# scartboard-rework.net
KiCad netlist of a schematic drawn in EAGLE
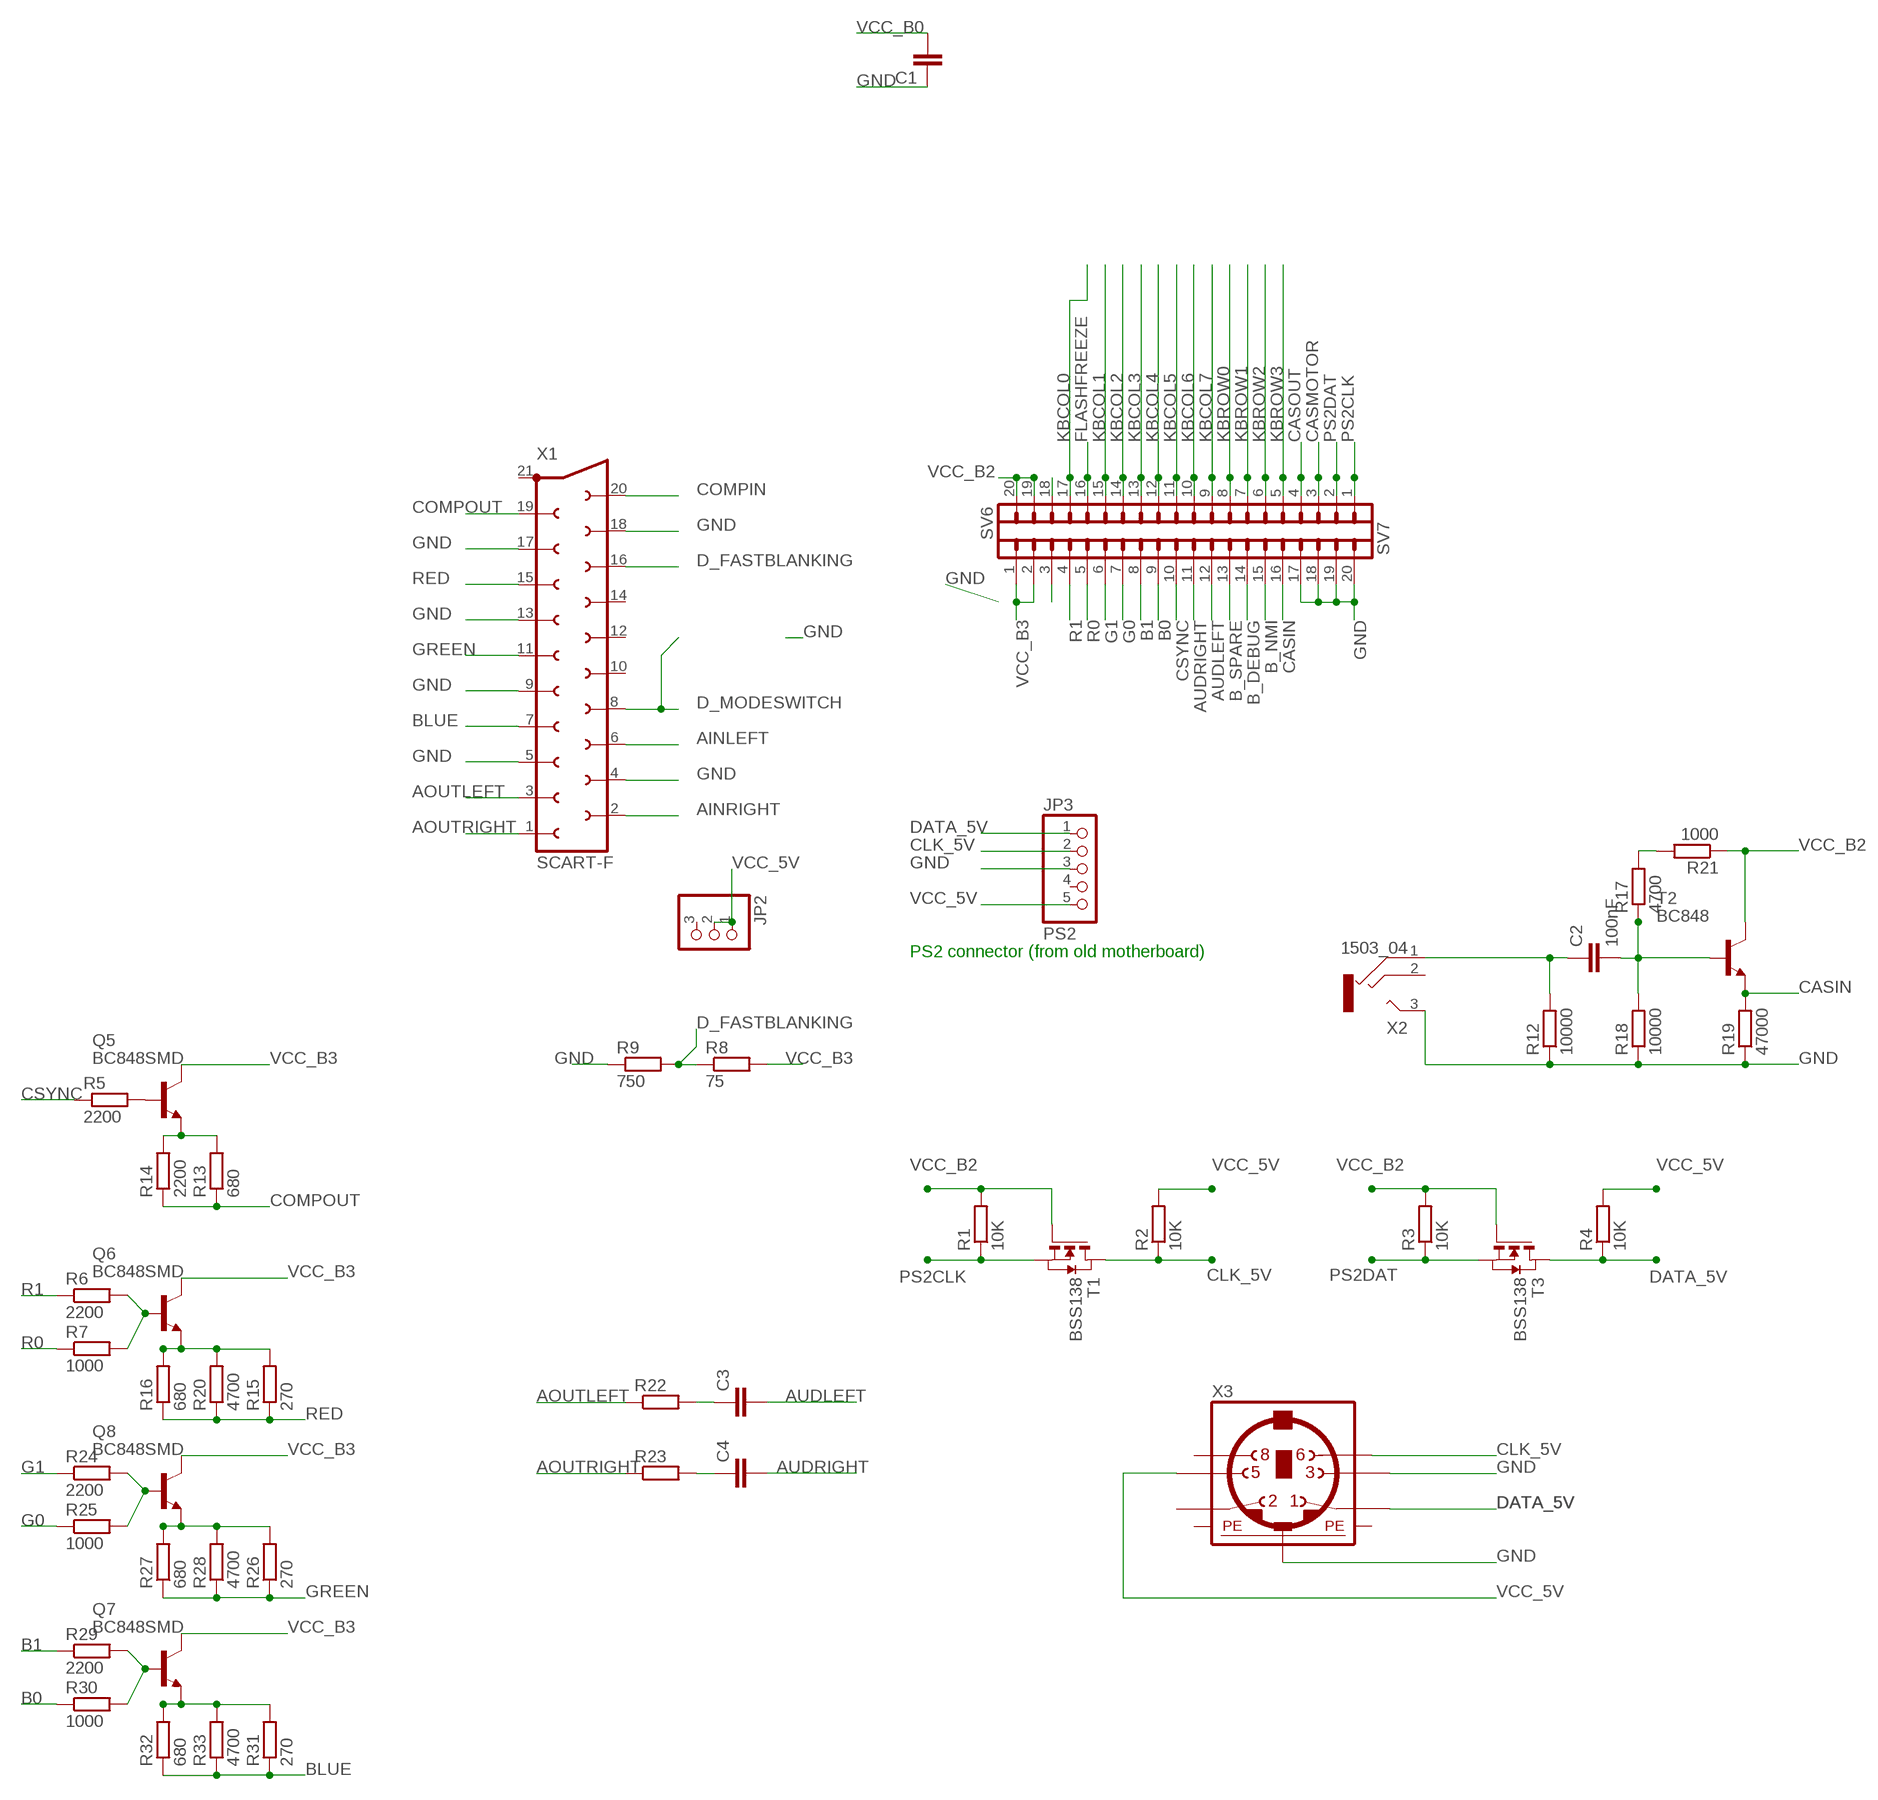
[diagram p0: schematic, sheet 1]

(export (version "E")
  (design (tool "Eeschema 10.0.6"))
  (components
    (comp (ref "C1")
      (value "C-EUC0603")
      (footprint "eagle-import:C0603")
      (libsource (lib "eagle-import") (part "C-EUC0603"))
    )
    (comp (ref "C2")
      (value "100nF")
      (footprint "eagle-import:C0603")
      (libsource (lib "eagle-import") (part "resistor_C-EUC0603"))
    )
    (comp (ref "C3")
      (value "C-EUC0603")
      (footprint "eagle-import:C0603")
      (libsource (lib "eagle-import") (part "resistor_C-EUC0603"))
    )
    (comp (ref "C4")
      (value "C-EUC0603")
      (footprint "eagle-import:C0603")
      (libsource (lib "eagle-import") (part "resistor_C-EUC0603"))
    )
    (comp (ref "JP2")
      (value "PINHD-1X3")
      (footprint "eagle-import:1X03")
      (libsource (lib "eagle-import") (part "PINHD-1X3"))
    )
    (comp (ref "JP3")
      (value "PS2")
      (footprint "eagle-import:1X05")
      (libsource (lib "eagle-import") (part "PINHD-1X5"))
    )
    (comp (ref "Q5")
      (value "BC848SMD")
      (footprint "eagle-import:SOT23")
      (libsource (lib "eagle-import") (part "BC848SMD"))
    )
    (comp (ref "Q6")
      (value "BC848SMD")
      (footprint "eagle-import:SOT23")
      (libsource (lib "eagle-import") (part "BC848SMD"))
    )
    (comp (ref "Q7")
      (value "BC848SMD")
      (footprint "eagle-import:SOT23")
      (libsource (lib "eagle-import") (part "BC848SMD"))
    )
    (comp (ref "Q8")
      (value "BC848SMD")
      (footprint "eagle-import:SOT23")
      (libsource (lib "eagle-import") (part "BC848SMD"))
    )
    (comp (ref "R1")
      (value "10K")
      (footprint "eagle-import:R0805")
      (libsource (lib "eagle-import") (part "R-EU_R0805"))
    )
    (comp (ref "R2")
      (value "10K")
      (footprint "eagle-import:R0805")
      (libsource (lib "eagle-import") (part "R-EU_R0805"))
    )
    (comp (ref "R3")
      (value "10K")
      (footprint "eagle-import:R0805")
      (libsource (lib "eagle-import") (part "R-EU_R0805"))
    )
    (comp (ref "R4")
      (value "10K")
      (footprint "eagle-import:R0805")
      (libsource (lib "eagle-import") (part "R-EU_R0805"))
    )
    (comp (ref "R5")
      (value "2200")
      (footprint "eagle-import:R0805")
      (libsource (lib "eagle-import") (part "R-EU_R0805"))
    )
    (comp (ref "R6")
      (value "2200")
      (footprint "eagle-import:R0805")
      (libsource (lib "eagle-import") (part "R-EU_R0805"))
    )
    (comp (ref "R7")
      (value "1000")
      (footprint "eagle-import:R0805")
      (libsource (lib "eagle-import") (part "R-EU_R0805"))
    )
    (comp (ref "R8")
      (value "75")
      (footprint "eagle-import:R0805")
      (libsource (lib "eagle-import") (part "R-EU_R0805"))
    )
    (comp (ref "R9")
      (value "750")
      (footprint "eagle-import:R0805")
      (libsource (lib "eagle-import") (part "R-EU_R0805"))
    )
    (comp (ref "R12")
      (value "10000")
      (footprint "eagle-import:R0805")
      (libsource (lib "eagle-import") (part "R-EU_R0805"))
    )
    (comp (ref "R13")
      (value "680")
      (footprint "eagle-import:R0805")
      (libsource (lib "eagle-import") (part "R-EU_R0805"))
    )
    (comp (ref "R14")
      (value "2200")
      (footprint "eagle-import:R0805")
      (libsource (lib "eagle-import") (part "R-EU_R0805"))
    )
    (comp (ref "R15")
      (value "270")
      (footprint "eagle-import:R0805")
      (libsource (lib "eagle-import") (part "R-EU_R0805"))
    )
    (comp (ref "R16")
      (value "680")
      (footprint "eagle-import:R0805")
      (libsource (lib "eagle-import") (part "R-EU_R0805"))
    )
    (comp (ref "R17")
      (value "4700")
      (footprint "eagle-import:R0805")
      (libsource (lib "eagle-import") (part "R-EU_R0805"))
    )
    (comp (ref "R18")
      (value "10000")
      (footprint "eagle-import:R0805")
      (libsource (lib "eagle-import") (part "R-EU_R0805"))
    )
    (comp (ref "R19")
      (value "47000")
      (footprint "eagle-import:R0805")
      (libsource (lib "eagle-import") (part "R-EU_R0805"))
    )
    (comp (ref "R20")
      (value "4700")
      (footprint "eagle-import:R0805")
      (libsource (lib "eagle-import") (part "R-EU_R0805"))
    )
    (comp (ref "R21")
      (value "1000")
      (footprint "eagle-import:R0805")
      (libsource (lib "eagle-import") (part "R-EU_R0805"))
    )
    (comp (ref "R22")
      (value "R-EU_M0805")
      (footprint "eagle-import:M0805")
      (libsource (lib "eagle-import") (part "resistor_R-EU_M0805"))
    )
    (comp (ref "R23")
      (value "R-EU_M0805")
      (footprint "eagle-import:M0805")
      (libsource (lib "eagle-import") (part "resistor_R-EU_M0805"))
    )
    (comp (ref "R24")
      (value "2200")
      (footprint "eagle-import:R0805")
      (libsource (lib "eagle-import") (part "R-EU_R0805"))
    )
    (comp (ref "R25")
      (value "1000")
      (footprint "eagle-import:R0805")
      (libsource (lib "eagle-import") (part "R-EU_R0805"))
    )
    (comp (ref "R26")
      (value "270")
      (footprint "eagle-import:R0805")
      (libsource (lib "eagle-import") (part "R-EU_R0805"))
    )
    (comp (ref "R27")
      (value "680")
      (footprint "eagle-import:R0805")
      (libsource (lib "eagle-import") (part "R-EU_R0805"))
    )
    (comp (ref "R28")
      (value "4700")
      (footprint "eagle-import:R0805")
      (libsource (lib "eagle-import") (part "R-EU_R0805"))
    )
    (comp (ref "R29")
      (value "2200")
      (footprint "eagle-import:R0805")
      (libsource (lib "eagle-import") (part "R-EU_R0805"))
    )
    (comp (ref "R30")
      (value "1000")
      (footprint "eagle-import:R0805")
      (libsource (lib "eagle-import") (part "R-EU_R0805"))
    )
    (comp (ref "R31")
      (value "270")
      (footprint "eagle-import:R0805")
      (libsource (lib "eagle-import") (part "R-EU_R0805"))
    )
    (comp (ref "R32")
      (value "680")
      (footprint "eagle-import:R0805")
      (libsource (lib "eagle-import") (part "R-EU_R0805"))
    )
    (comp (ref "R33")
      (value "4700")
      (footprint "eagle-import:R0805")
      (libsource (lib "eagle-import") (part "R-EU_R0805"))
    )
    (comp (ref "SV6")
      (value "MA20-1")
      (footprint "eagle-import:MA20-1")
      (libsource (lib "eagle-import") (part "MA20-1"))
    )
    (comp (ref "SV7")
      (value "MA20-1")
      (footprint "eagle-import:MA20-1")
      (libsource (lib "eagle-import") (part "MA20-1"))
    )
    (comp (ref "T1")
      (value "BSS138")
      (footprint "eagle-import:SOT-23")
      (libsource (lib "eagle-import") (part "NMOSSOT23"))
    )
    (comp (ref "T2")
      (value "BC848")
      (footprint "eagle-import:SOT23")
      (libsource (lib "eagle-import") (part "BC848"))
    )
    (comp (ref "T3")
      (value "BSS138")
      (footprint "eagle-import:SOT-23")
      (libsource (lib "eagle-import") (part "NMOSSOT23"))
    )
    (comp (ref "X1")
      (value "SCART-F")
      (footprint "eagle-import:SCART-F")
      (libsource (lib "eagle-import") (part "SCART-F"))
    )
    (comp (ref "X2")
      (value "1503_04")
      (footprint "eagle-import:1503_04")
      (libsource (lib "eagle-import") (part "1503_04"))
    )
    (comp (ref "X3")
      (value "MINI_DIN_6")
      (footprint "eagle-import:M_DIN6")
      (libsource (lib "eagle-import") (part "MINI_DIN_6"))
    )
  )
  (nets
    (net (code "1") (name "/AINLEFT") (class "Default")
      (node (ref "X1") (pin "6") (pinfunction "6_6") (pintype "passive"))
    )
    (net (code "2") (name "/AINRIGHT") (class "Default")
      (node (ref "X1") (pin "2") (pinfunction "2_2") (pintype "passive"))
    )
    (net (code "3") (name "/AOUTLEFT") (class "Default")
      (node (ref "R22") (pin "1") (pinfunction "1_1") (pintype "passive"))
      (node (ref "X1") (pin "3") (pinfunction "3_3") (pintype "passive"))
    )
    (net (code "4") (name "/AOUTRIGHT") (class "Default")
      (node (ref "R23") (pin "1") (pinfunction "1_1") (pintype "passive"))
      (node (ref "X1") (pin "1") (pinfunction "1_1") (pintype "passive"))
    )
    (net (code "5") (name "/AUDLEFT") (class "Default")
      (node (ref "C3") (pin "2") (pinfunction "2_2") (pintype "passive"))
      (node (ref "SV7") (pin "12") (pinfunction "12_12") (pintype "passive"))
    )
    (net (code "6") (name "/AUDRIGHT") (class "Default")
      (node (ref "C4") (pin "2") (pinfunction "2_2") (pintype "passive"))
      (node (ref "SV7") (pin "11") (pinfunction "11_11") (pintype "passive"))
    )
    (net (code "7") (name "/B0") (class "Default")
      (node (ref "R30") (pin "1") (pinfunction "1_1") (pintype "passive"))
      (node (ref "SV7") (pin "9") (pinfunction "9_9") (pintype "passive"))
    )
    (net (code "8") (name "/B1") (class "Default")
      (node (ref "R29") (pin "1") (pinfunction "1_1") (pintype "passive"))
      (node (ref "SV7") (pin "8") (pinfunction "8_8") (pintype "passive"))
    )
    (net (code "9") (name "/BLUE") (class "Default")
      (node (ref "R31") (pin "1") (pinfunction "1_1") (pintype "passive"))
      (node (ref "R32") (pin "1") (pinfunction "1_1") (pintype "passive"))
      (node (ref "R33") (pin "1") (pinfunction "1_1") (pintype "passive"))
      (node (ref "X1") (pin "7") (pinfunction "7_7") (pintype "passive"))
    )
    (net (code "10") (name "/B_DEBUG") (class "Default")
      (node (ref "SV7") (pin "14") (pinfunction "14_14") (pintype "passive"))
    )
    (net (code "11") (name "/B_NMI") (class "Default")
      (node (ref "SV7") (pin "15") (pinfunction "15_15") (pintype "passive"))
    )
    (net (code "12") (name "/B_SPARE") (class "Default")
      (node (ref "SV7") (pin "13") (pinfunction "13_13") (pintype "passive"))
    )
    (net (code "13") (name "/CASIN") (class "Default")
      (node (ref "R19") (pin "2") (pinfunction "2_2") (pintype "passive"))
      (node (ref "SV7") (pin "16") (pinfunction "16_16") (pintype "passive"))
      (node (ref "T2") (pin "2") (pinfunction "E_2") (pintype "passive"))
    )
    (net (code "14") (name "/CASMOTOR") (class "Default")
      (node (ref "SV6") (pin "3") (pinfunction "3_3") (pintype "passive"))
    )
    (net (code "15") (name "/CASOUT") (class "Default")
      (node (ref "SV6") (pin "4") (pinfunction "4_4") (pintype "passive"))
    )
    (net (code "16") (name "/CLK_5V") (class "Default")
      (node (ref "JP3") (pin "2") (pinfunction "2_2") (pintype "passive"))
      (node (ref "R2") (pin "1") (pinfunction "1_1") (pintype "passive"))
      (node (ref "T1") (pin "1") (pinfunction "D_1") (pintype "passive"))
      (node (ref "X3") (pin "6") (pinfunction "6_6") (pintype "passive"))
    )
    (net (code "17") (name "/COMPIN") (class "Default")
      (node (ref "X1") (pin "20") (pinfunction "20_20") (pintype "passive"))
    )
    (net (code "18") (name "/COMPOUT") (class "Default")
      (node (ref "R13") (pin "1") (pinfunction "1_1") (pintype "passive"))
      (node (ref "R14") (pin "1") (pinfunction "1_1") (pintype "passive"))
      (node (ref "X1") (pin "19") (pinfunction "19_19") (pintype "passive"))
    )
    (net (code "19") (name "/CSYNC") (class "Default")
      (node (ref "R5") (pin "1") (pinfunction "1_1") (pintype "passive"))
      (node (ref "SV7") (pin "10") (pinfunction "10_10") (pintype "passive"))
    )
    (net (code "20") (name "/DATA_5V") (class "Default")
      (node (ref "JP3") (pin "1") (pinfunction "1_1") (pintype "passive"))
      (node (ref "R4") (pin "1") (pinfunction "1_1") (pintype "passive"))
      (node (ref "T3") (pin "1") (pinfunction "D_1") (pintype "passive"))
      (node (ref "X3") (pin "1") (pinfunction "1_1") (pintype "passive"))
    )
    (net (code "21") (name "/D_FASTBLANKING") (class "Default")
      (node (ref "R8") (pin "1") (pinfunction "1_1") (pintype "passive"))
      (node (ref "R9") (pin "2") (pinfunction "2_2") (pintype "passive"))
      (node (ref "X1") (pin "16") (pinfunction "16_16") (pintype "passive"))
    )
    (net (code "22") (name "/D_MODESWITCH") (class "Default")
      (node (ref "X1") (pin "8") (pinfunction "8_8") (pintype "passive"))
    )
    (net (code "23") (name "/FLASHFREEZE") (class "Default")
      (node (ref "SV6") (pin "16") (pinfunction "16_16") (pintype "passive"))
    )
    (net (code "24") (name "/G0") (class "Default")
      (node (ref "R25") (pin "1") (pinfunction "1_1") (pintype "passive"))
      (node (ref "SV7") (pin "7") (pinfunction "7_7") (pintype "passive"))
    )
    (net (code "25") (name "/G1") (class "Default")
      (node (ref "R24") (pin "1") (pinfunction "1_1") (pintype "passive"))
      (node (ref "SV7") (pin "6") (pinfunction "6_6") (pintype "passive"))
    )
    (net (code "26") (name "/GND") (class "Default")
      (node (ref "C1") (pin "1") (pinfunction "1_1") (pintype "passive"))
      (node (ref "JP3") (pin "3") (pinfunction "3_3") (pintype "passive"))
      (node (ref "R12") (pin "1") (pinfunction "1_1") (pintype "passive"))
      (node (ref "R18") (pin "1") (pinfunction "1_1") (pintype "passive"))
      (node (ref "R19") (pin "1") (pinfunction "1_1") (pintype "passive"))
      (node (ref "R9") (pin "1") (pinfunction "1_1") (pintype "passive"))
      (node (ref "SV7") (pin "17") (pinfunction "17_17") (pintype "passive"))
      (node (ref "SV7") (pin "18") (pinfunction "18_18") (pintype "passive"))
      (node (ref "SV7") (pin "19") (pinfunction "19_19") (pintype "passive"))
      (node (ref "SV7") (pin "20") (pinfunction "20_20") (pintype "passive"))
      (node (ref "X1") (pin "13") (pinfunction "13_13") (pintype "passive"))
      (node (ref "X1") (pin "17") (pinfunction "17_17") (pintype "passive"))
      (node (ref "X1") (pin "18") (pinfunction "18_18") (pintype "passive"))
      (node (ref "X1") (pin "4") (pinfunction "4_4") (pintype "passive"))
      (node (ref "X1") (pin "5") (pinfunction "5_5") (pintype "passive"))
      (node (ref "X1") (pin "9") (pinfunction "9_9") (pintype "passive"))
      (node (ref "X2") (pin "3") (pinfunction "2_3") (pintype "passive"))
      (node (ref "X3") (pin "3") (pinfunction "3_3") (pintype "passive"))
      (node (ref "X3") (pin "SH2") (pinfunction "PE2_SH2") (pintype "power_in"))
    )
    (net (code "27") (name "/GREEN") (class "Default")
      (node (ref "R26") (pin "1") (pinfunction "1_1") (pintype "passive"))
      (node (ref "R27") (pin "1") (pinfunction "1_1") (pintype "passive"))
      (node (ref "R28") (pin "1") (pinfunction "1_1") (pintype "passive"))
      (node (ref "X1") (pin "11") (pinfunction "11_11") (pintype "passive"))
    )
    (net (code "28") (name "/KBCOL0") (class "Default")
      (node (ref "SV6") (pin "17") (pinfunction "17_17") (pintype "passive"))
    )
    (net (code "29") (name "/KBCOL1") (class "Default")
      (node (ref "SV6") (pin "15") (pinfunction "15_15") (pintype "passive"))
    )
    (net (code "30") (name "/KBCOL2") (class "Default")
      (node (ref "SV6") (pin "14") (pinfunction "14_14") (pintype "passive"))
    )
    (net (code "31") (name "/KBCOL3") (class "Default")
      (node (ref "SV6") (pin "13") (pinfunction "13_13") (pintype "passive"))
    )
    (net (code "32") (name "/KBCOL4") (class "Default")
      (node (ref "SV6") (pin "12") (pinfunction "12_12") (pintype "passive"))
    )
    (net (code "33") (name "/KBCOL5") (class "Default")
      (node (ref "SV6") (pin "11") (pinfunction "11_11") (pintype "passive"))
    )
    (net (code "34") (name "/KBCOL6") (class "Default")
      (node (ref "SV6") (pin "10") (pinfunction "10_10") (pintype "passive"))
    )
    (net (code "35") (name "/KBCOL7") (class "Default")
      (node (ref "SV6") (pin "9") (pinfunction "9_9") (pintype "passive"))
    )
    (net (code "36") (name "/KBROW0") (class "Default")
      (node (ref "SV6") (pin "8") (pinfunction "8_8") (pintype "passive"))
    )
    (net (code "37") (name "/KBROW1") (class "Default")
      (node (ref "SV6") (pin "7") (pinfunction "7_7") (pintype "passive"))
    )
    (net (code "38") (name "/KBROW2") (class "Default")
      (node (ref "SV6") (pin "6") (pinfunction "6_6") (pintype "passive"))
    )
    (net (code "39") (name "/KBROW3") (class "Default")
      (node (ref "SV6") (pin "5") (pinfunction "5_5") (pintype "passive"))
    )
    (net (code "40") (name "/PE1") (class "Default")
      (node (ref "X3") (pin "SH1") (pinfunction "PE1_SH1") (pintype "power_in"))
    )
    (net (code "41") (name "/PE3") (class "Default")
      (node (ref "X3") (pin "SH3") (pinfunction "PE3_SH3") (pintype "power_in"))
    )
    (net (code "42") (name "/PS2CLK") (class "Default")
      (node (ref "R1") (pin "1") (pinfunction "1_1") (pintype "passive"))
      (node (ref "SV6") (pin "1") (pinfunction "1_1") (pintype "passive"))
      (node (ref "T1") (pin "2") (pinfunction "S_2") (pintype "passive"))
    )
    (net (code "43") (name "/PS2DAT") (class "Default")
      (node (ref "R3") (pin "1") (pinfunction "1_1") (pintype "passive"))
      (node (ref "SV6") (pin "2") (pinfunction "2_2") (pintype "passive"))
      (node (ref "T3") (pin "2") (pinfunction "S_2") (pintype "passive"))
    )
    (net (code "44") (name "/R0") (class "Default")
      (node (ref "R7") (pin "1") (pinfunction "1_1") (pintype "passive"))
      (node (ref "SV7") (pin "5") (pinfunction "5_5") (pintype "passive"))
    )
    (net (code "45") (name "/R1") (class "Default")
      (node (ref "R6") (pin "1") (pinfunction "1_1") (pintype "passive"))
      (node (ref "SV7") (pin "4") (pinfunction "4_4") (pintype "passive"))
    )
    (net (code "46") (name "/RED") (class "Default")
      (node (ref "R15") (pin "1") (pinfunction "1_1") (pintype "passive"))
      (node (ref "R16") (pin "1") (pinfunction "1_1") (pintype "passive"))
      (node (ref "R20") (pin "1") (pinfunction "1_1") (pintype "passive"))
      (node (ref "X1") (pin "15") (pinfunction "15_15") (pintype "passive"))
    )
    (net (code "47") (name "/VCC_5V") (class "Default")
      (node (ref "JP2") (pin "1") (pinfunction "1_1") (pintype "passive"))
      (node (ref "JP2") (pin "2") (pinfunction "2_2") (pintype "passive"))
      (node (ref "JP3") (pin "5") (pinfunction "5_5") (pintype "passive"))
      (node (ref "R2") (pin "2") (pinfunction "2_2") (pintype "passive"))
      (node (ref "R4") (pin "2") (pinfunction "2_2") (pintype "passive"))
      (node (ref "X3") (pin "5") (pinfunction "5_5") (pintype "passive"))
    )
    (net (code "48") (name "/VCC_B0") (class "Default")
      (node (ref "C1") (pin "2") (pinfunction "2_2") (pintype "passive"))
    )
    (net (code "49") (name "/VCC_B2") (class "Default")
      (node (ref "R1") (pin "2") (pinfunction "2_2") (pintype "passive"))
      (node (ref "R21") (pin "1") (pinfunction "1_1") (pintype "passive"))
      (node (ref "R3") (pin "2") (pinfunction "2_2") (pintype "passive"))
      (node (ref "SV6") (pin "19") (pinfunction "19_19") (pintype "passive"))
      (node (ref "SV6") (pin "20") (pinfunction "20_20") (pintype "passive"))
      (node (ref "T1") (pin "3") (pinfunction "G_3") (pintype "passive"))
      (node (ref "T2") (pin "3") (pinfunction "C_3") (pintype "passive"))
      (node (ref "T3") (pin "3") (pinfunction "G_3") (pintype "passive"))
    )
    (net (code "50") (name "/VCC_B3") (class "Default")
      (node (ref "Q5") (pin "3") (pinfunction "C_3") (pintype "passive"))
      (node (ref "Q6") (pin "3") (pinfunction "C_3") (pintype "passive"))
      (node (ref "Q7") (pin "3") (pinfunction "C_3") (pintype "passive"))
      (node (ref "Q8") (pin "3") (pinfunction "C_3") (pintype "passive"))
      (node (ref "R8") (pin "2") (pinfunction "2_2") (pintype "passive"))
      (node (ref "SV7") (pin "1") (pinfunction "1_1") (pintype "passive"))
      (node (ref "SV7") (pin "2") (pinfunction "2_2") (pintype "passive"))
    )
    (net (code "51") (name "Net-(C2-Pad1)") (class "Default")
      (node (ref "C2") (pin "1") (pinfunction "1_1") (pintype "passive"))
      (node (ref "R12") (pin "2") (pinfunction "2_2") (pintype "passive"))
      (node (ref "X2") (pin "1") (pinfunction "1_1") (pintype "passive"))
    )
    (net (code "52") (name "Net-(C3-Pad1)") (class "Default")
      (node (ref "C3") (pin "1") (pinfunction "1_1") (pintype "passive"))
      (node (ref "R22") (pin "2") (pinfunction "2_2") (pintype "passive"))
    )
    (net (code "53") (name "Net-(C4-Pad1)") (class "Default")
      (node (ref "C4") (pin "1") (pinfunction "1_1") (pintype "passive"))
      (node (ref "R23") (pin "2") (pinfunction "2_2") (pintype "passive"))
    )
    (net (code "54") (name "Net-(Q5-B)") (class "Default")
      (node (ref "Q5") (pin "1") (pinfunction "B_1") (pintype "passive"))
      (node (ref "R5") (pin "2") (pinfunction "2_2") (pintype "passive"))
    )
    (net (code "55") (name "Net-(Q5-E)") (class "Default")
      (node (ref "Q5") (pin "2") (pinfunction "E_2") (pintype "passive"))
      (node (ref "R13") (pin "2") (pinfunction "2_2") (pintype "passive"))
      (node (ref "R14") (pin "2") (pinfunction "2_2") (pintype "passive"))
    )
    (net (code "56") (name "Net-(Q6-B)") (class "Default")
      (node (ref "Q6") (pin "1") (pinfunction "B_1") (pintype "passive"))
      (node (ref "R6") (pin "2") (pinfunction "2_2") (pintype "passive"))
      (node (ref "R7") (pin "2") (pinfunction "2_2") (pintype "passive"))
    )
    (net (code "57") (name "Net-(Q6-E)") (class "Default")
      (node (ref "Q6") (pin "2") (pinfunction "E_2") (pintype "passive"))
      (node (ref "R15") (pin "2") (pinfunction "2_2") (pintype "passive"))
      (node (ref "R16") (pin "2") (pinfunction "2_2") (pintype "passive"))
      (node (ref "R20") (pin "2") (pinfunction "2_2") (pintype "passive"))
    )
    (net (code "58") (name "Net-(Q7-B)") (class "Default")
      (node (ref "Q7") (pin "1") (pinfunction "B_1") (pintype "passive"))
      (node (ref "R29") (pin "2") (pinfunction "2_2") (pintype "passive"))
      (node (ref "R30") (pin "2") (pinfunction "2_2") (pintype "passive"))
    )
    (net (code "59") (name "Net-(Q7-E)") (class "Default")
      (node (ref "Q7") (pin "2") (pinfunction "E_2") (pintype "passive"))
      (node (ref "R31") (pin "2") (pinfunction "2_2") (pintype "passive"))
      (node (ref "R32") (pin "2") (pinfunction "2_2") (pintype "passive"))
      (node (ref "R33") (pin "2") (pinfunction "2_2") (pintype "passive"))
    )
    (net (code "60") (name "Net-(Q8-B)") (class "Default")
      (node (ref "Q8") (pin "1") (pinfunction "B_1") (pintype "passive"))
      (node (ref "R24") (pin "2") (pinfunction "2_2") (pintype "passive"))
      (node (ref "R25") (pin "2") (pinfunction "2_2") (pintype "passive"))
    )
    (net (code "61") (name "Net-(Q8-E)") (class "Default")
      (node (ref "Q8") (pin "2") (pinfunction "E_2") (pintype "passive"))
      (node (ref "R26") (pin "2") (pinfunction "2_2") (pintype "passive"))
      (node (ref "R27") (pin "2") (pinfunction "2_2") (pintype "passive"))
      (node (ref "R28") (pin "2") (pinfunction "2_2") (pintype "passive"))
    )
    (net (code "62") (name "Net-(R17-Pad2)") (class "Default")
      (node (ref "R17") (pin "2") (pinfunction "2_2") (pintype "passive"))
      (node (ref "R21") (pin "2") (pinfunction "2_2") (pintype "passive"))
    )
    (net (code "63") (name "Net-(T2-B)") (class "Default")
      (node (ref "C2") (pin "2") (pinfunction "2_2") (pintype "passive"))
      (node (ref "R17") (pin "1") (pinfunction "1_1") (pintype "passive"))
      (node (ref "R18") (pin "2") (pinfunction "2_2") (pintype "passive"))
      (node (ref "T2") (pin "1") (pinfunction "B_1") (pintype "passive"))
    )
    (net (code "64") (name "unconnected-(JP2-Pad3)") (class "Default")
      (node (ref "JP2") (pin "3") (pinfunction "3_3") (pintype "passive"))
    )
    (net (code "65") (name "unconnected-(JP3-Pad4)") (class "Default")
      (node (ref "JP3") (pin "4") (pinfunction "4_4") (pintype "passive"))
    )
    (net (code "66") (name "unconnected-(SV6-Pad18)") (class "Default")
      (node (ref "SV6") (pin "18") (pinfunction "18_18") (pintype "passive"))
    )
    (net (code "67") (name "unconnected-(SV7-Pad3)") (class "Default")
      (node (ref "SV7") (pin "3") (pinfunction "3_3") (pintype "passive"))
    )
    (net (code "68") (name "unconnected-(X1-Pad10)") (class "Default")
      (node (ref "X1") (pin "10") (pinfunction "10_10") (pintype "passive"))
    )
    (net (code "69") (name "unconnected-(X1-Pad12)") (class "Default")
      (node (ref "X1") (pin "12") (pinfunction "12_12") (pintype "passive"))
    )
    (net (code "70") (name "unconnected-(X1-Pad14)") (class "Default")
      (node (ref "X1") (pin "14") (pinfunction "14_14") (pintype "passive"))
    )
    (net (code "71") (name "unconnected-(X1-Pad21)") (class "Default")
      (node (ref "X1") (pin "21") (pinfunction "21_21") (pintype "passive"))
    )
    (net (code "72") (name "unconnected-(X2-3-Pad2)") (class "Default")
      (node (ref "X2") (pin "2") (pinfunction "3_2") (pintype "passive"))
    )
    (net (code "73") (name "unconnected-(X3-Pad2)") (class "Default")
      (node (ref "X3") (pin "2") (pinfunction "2_2") (pintype "passive"))
    )
    (net (code "74") (name "unconnected-(X3-Pad8)") (class "Default")
      (node (ref "X3") (pin "8") (pinfunction "8_8") (pintype "passive"))
    )
  )
)
